# 3.net
KiCad netlist of a schematic drawn in Altium Designer
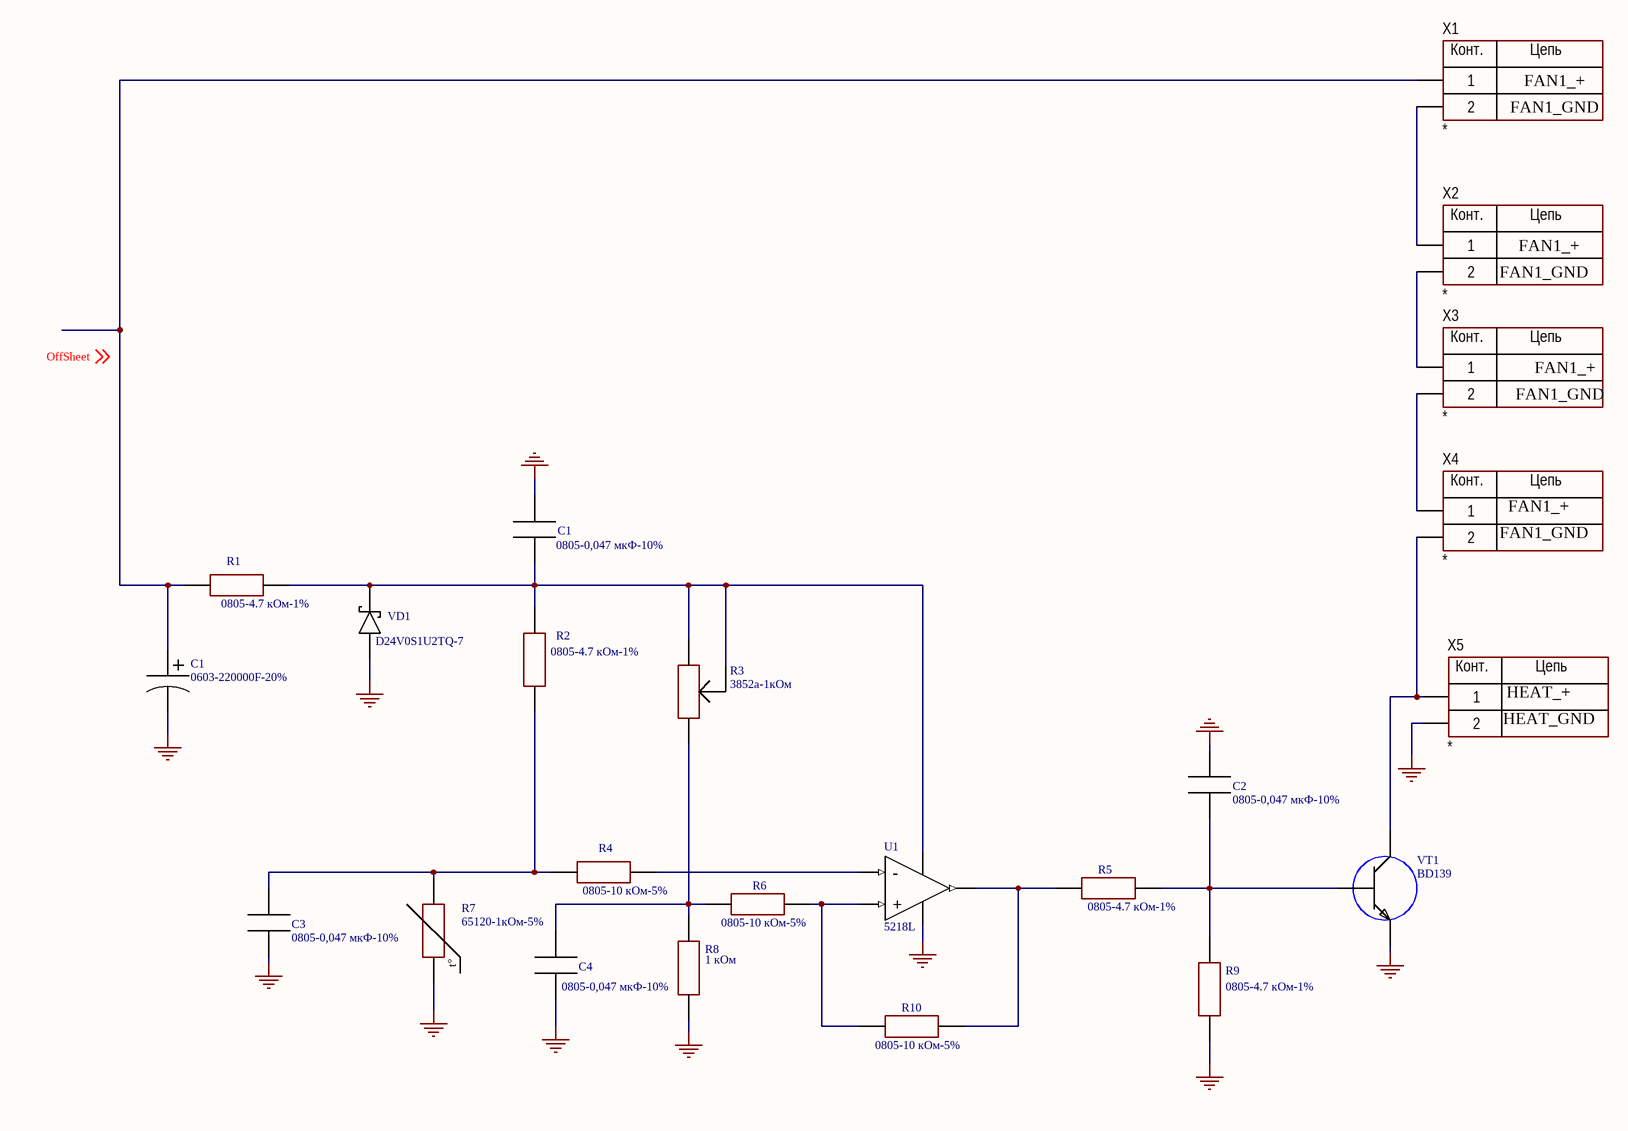
[diagram p0: Э3.SchDoc]

(export (version "E")
  (design (tool "Eeschema 10.0.6"))
  (components
    (comp (ref "C1")
      (value "0805-0,047 мкФ-10%")
      (footprint "PCBComponent_1")
      (description "Condensator_SDM_0805")
      (libsource (lib "Резистор 0805") (part "condensator"))
    )
    (comp (ref "C2")
      (value "0805-0,047 мкФ-10%")
      (footprint "PCBComponent_1")
      (description "Condensator_SDM_0805")
      (libsource (lib "Резистор 0805") (part "condensator"))
    )
    (comp (ref "C3")
      (value "0805-0,047 мкФ-10%")
      (footprint "PCBComponent_1")
      (description "Condensator_SDM_0805")
      (libsource (lib "Резистор 0805") (part "condensator"))
    )
    (comp (ref "C4")
      (value "0805-0,047 мкФ-10%")
      (footprint "PCBComponent_1")
      (description "Condensator_SDM_0805")
      (libsource (lib "Резистор 0805") (part "condensator"))
    )
    (comp (ref "R1")
      (value "0805-4.7 кОм-1%")
      (footprint "Resistor SMD 0805")
      (libsource (lib "") (part "resistor_SMD0805_1"))
    )
    (comp (ref "R2")
      (value "0805-4.7 кОм-1%")
      (footprint "Resistor SMD 0805")
      (libsource (lib "Резистор 0805") (part "resistor_SMD0805"))
    )
    (comp (ref "R3")
      (value "3852a-1кОм")
      (footprint "adj")
      (libsource (lib "Резистор 0805") (part "resistor peremen"))
    )
    (comp (ref "R4")
      (value "0805-10 кОм-5%")
      (footprint "Resistor SMD 0805")
      (libsource (lib "") (part "resistor_SMD0805_1"))
    )
    (comp (ref "R5")
      (value "0805-4.7 кОм-1%")
      (footprint "Resistor SMD 0805")
      (libsource (lib "") (part "resistor_SMD0805_1"))
    )
    (comp (ref "R6")
      (value "0805-10 кОм-5%")
      (footprint "Resistor SMD 0805")
      (libsource (lib "") (part "resistor_SMD0805_1"))
    )
    (comp (ref "R7")
      (value "65120-1кОм-5%")
      (footprint "Resistor SMD 0805")
      (libsource (lib "Резистор 0805") (part "resistor temerature"))
    )
    (comp (ref "R8")
      (value "1 кОм")
      (footprint "Resistor SMD 0805")
      (libsource (lib "Резистор 0805") (part "resistor_SMD0805"))
    )
    (comp (ref "R9")
      (value "0805-4.7 кОм-1%")
      (footprint "Resistor SMD 0805")
      (libsource (lib "Резистор 0805") (part "resistor_SMD0805"))
    )
    (comp (ref "R10")
      (value "0805-10 кОм-5%")
      (footprint "Resistor SMD 0805")
      (libsource (lib "") (part "resistor_SMD0805_1"))
    )
    (comp (ref "U1")
      (value "5218L")
      (footprint "PCBComponent_1 - duplicate4")
      (libsource (lib "Резистор 0805") (part "operasion_ysil"))
    )
    (comp (ref "VD1")
      (value "diod_stabilitron")
      (footprint "PCBComponent_1 - duplicate1")
      (description "diod")
      (fields (field (name "PARTNAMBER") "D24V0S1U2TQ-7"))
      (libsource (lib "Резистор 0805") (part "diod_stabilitron"))
    )
    (comp (ref "VT1")
      (value "BD139")
      (footprint "transistor")
      (libsource (lib "Резистор 0805") (part "transistor"))
    )
    (comp (ref "X1")
      (value "*")
      (footprint "custom:CON: 300-02P-5.0")
      (libsource (lib "Connectors") (part "2-Connector"))
    )
    (comp (ref "X2")
      (value "*")
      (footprint "custom:CON: 300-02P-5.0")
      (libsource (lib "Connectors") (part "2-Connector"))
    )
    (comp (ref "X3")
      (value "*")
      (footprint "custom:CON: 300-02P-5.0")
      (libsource (lib "Connectors") (part "2-Connector"))
    )
    (comp (ref "X4")
      (value "*")
      (footprint "custom:CON: 300-02P-5.0")
      (libsource (lib "Connectors") (part "2-Connector"))
    )
    (comp (ref "X5")
      (value "*")
      (footprint "custom:CON: 300-02P-5.0")
      (libsource (lib "Connectors") (part "2-Connector"))
    )
    (comp (ref "С1")
      (value "0603-220000F-20%")
      (footprint "PCBComponent_1 - duplicate2")
      (description "220000UF 20% 100V")
      (libsource (lib "Резистор 0805") (part "condensator+"))
    )
  )
  (nets
    (net (code "1") (name "<NO NET>") (class "Default")
      (node (ref "C1") (pin "1") (pinfunction "2_1") (pintype "passive"))
      (node (ref "C2") (pin "1") (pinfunction "2_1") (pintype "passive"))
      (node (ref "C3") (pin "2") (pinfunction "3_2") (pintype "passive"))
      (node (ref "C4") (pin "2") (pinfunction "3_2") (pintype "passive"))
      (node (ref "R7") (pin "2") (pinfunction "3_2") (pintype "passive"))
      (node (ref "R8") (pin "1") (pinfunction "3_1") (pintype "passive"))
      (node (ref "R9") (pin "1") (pinfunction "3_1") (pintype "passive"))
      (node (ref "U1") (pin "4") (pinfunction "GND_4") (pintype "passive"))
      (node (ref "VD1") (pin "2") (pinfunction "3_2") (pintype "passive"))
      (node (ref "VT1") (pin "3") (pinfunction "3_3") (pintype "passive"))
      (node (ref "X5") (pin "2") (pinfunction "2_2") (pintype "passive"))
      (node (ref "С1") (pin "2") (pinfunction "2_2") (pintype "passive"))
    )
    (net (code "2") (name "Net-(C1-3)") (class "Default")
      (node (ref "C1") (pin "2") (pinfunction "3_2") (pintype "passive"))
      (node (ref "R1") (pin "2") (pinfunction "2_2") (pintype "passive"))
      (node (ref "R2") (pin "2") (pinfunction "2_2") (pintype "passive"))
      (node (ref "R3") (pin "1") (pinfunction "2_1") (pintype "passive"))
      (node (ref "R3") (pin "2") (pinfunction "2_2") (pintype "passive"))
      (node (ref "U1") (pin "8") (pinfunction "VCC_8") (pintype "passive"))
      (node (ref "VD1") (pin "1") (pinfunction "3_1") (pintype "passive"))
    )
    (net (code "3") (name "Net-(C2-3)") (class "Default")
      (node (ref "C2") (pin "2") (pinfunction "3_2") (pintype "passive"))
      (node (ref "R5") (pin "2") (pinfunction "2_2") (pintype "passive"))
      (node (ref "R9") (pin "2") (pinfunction "2_2") (pintype "passive"))
      (node (ref "VT1") (pin "2") (pinfunction "4_2") (pintype "passive"))
    )
    (net (code "4") (name "Net-(C3-2)") (class "Default")
      (node (ref "C3") (pin "1") (pinfunction "2_1") (pintype "passive"))
      (node (ref "R2") (pin "1") (pinfunction "3_1") (pintype "passive"))
      (node (ref "R4") (pin "1") (pinfunction "3_1") (pintype "passive"))
      (node (ref "R7") (pin "1") (pinfunction "3_1") (pintype "passive"))
    )
    (net (code "5") (name "Net-(C4-2)") (class "Default")
      (node (ref "C4") (pin "1") (pinfunction "2_1") (pintype "passive"))
      (node (ref "R3") (pin "3") (pinfunction "3_3") (pintype "passive"))
      (node (ref "R6") (pin "1") (pinfunction "3_1") (pintype "passive"))
      (node (ref "R8") (pin "2") (pinfunction "2_2") (pintype "passive"))
    )
    (net (code "6") (name "Net-(R1-3)") (class "Default")
      (node (ref "R1") (pin "1") (pinfunction "3_1") (pintype "passive"))
      (node (ref "X1") (pin "1") (pinfunction "1_1") (pintype "passive"))
      (node (ref "С1") (pin "1") (pinfunction "3_1") (pintype "passive"))
    )
    (net (code "7") (name "Net-(R5-3)") (class "Default")
      (node (ref "R10") (pin "2") (pinfunction "2_2") (pintype "passive"))
      (node (ref "R5") (pin "1") (pinfunction "3_1") (pintype "passive"))
      (node (ref "U1") (pin "1") (pinfunction "0_1") (pintype "output"))
    )
    (net (code "8") (name "Net-(R10-3)") (class "Default")
      (node (ref "R10") (pin "1") (pinfunction "3_1") (pintype "passive"))
      (node (ref "R6") (pin "2") (pinfunction "2_2") (pintype "passive"))
      (node (ref "U1") (pin "3") (pinfunction "+_3") (pintype "input"))
    )
    (net (code "9") (name "Net-(U1--)") (class "Default")
      (node (ref "R4") (pin "2") (pinfunction "2_2") (pintype "passive"))
      (node (ref "U1") (pin "2") (pinfunction "-_2") (pintype "input"))
    )
    (net (code "10") (name "Net-(VT1-3-Pad1)") (class "Default")
      (node (ref "VT1") (pin "1") (pinfunction "3_1") (pintype "passive"))
      (node (ref "X4") (pin "2") (pinfunction "2_2") (pintype "passive"))
      (node (ref "X5") (pin "1") (pinfunction "1_1") (pintype "passive"))
    )
    (net (code "11") (name "Net-(X1-Pad2)") (class "Default")
      (node (ref "X1") (pin "2") (pinfunction "2_2") (pintype "passive"))
      (node (ref "X2") (pin "1") (pinfunction "1_1") (pintype "passive"))
    )
    (net (code "12") (name "Net-(X2-Pad2)") (class "Default")
      (node (ref "X2") (pin "2") (pinfunction "2_2") (pintype "passive"))
      (node (ref "X3") (pin "1") (pinfunction "1_1") (pintype "passive"))
    )
    (net (code "13") (name "Net-(X3-Pad2)") (class "Default")
      (node (ref "X3") (pin "2") (pinfunction "2_2") (pintype "passive"))
      (node (ref "X4") (pin "1") (pinfunction "1_1") (pintype "passive"))
    )
  )
)
